# MCU.net
KiCad netlist of a schematic drawn in Altium Designer
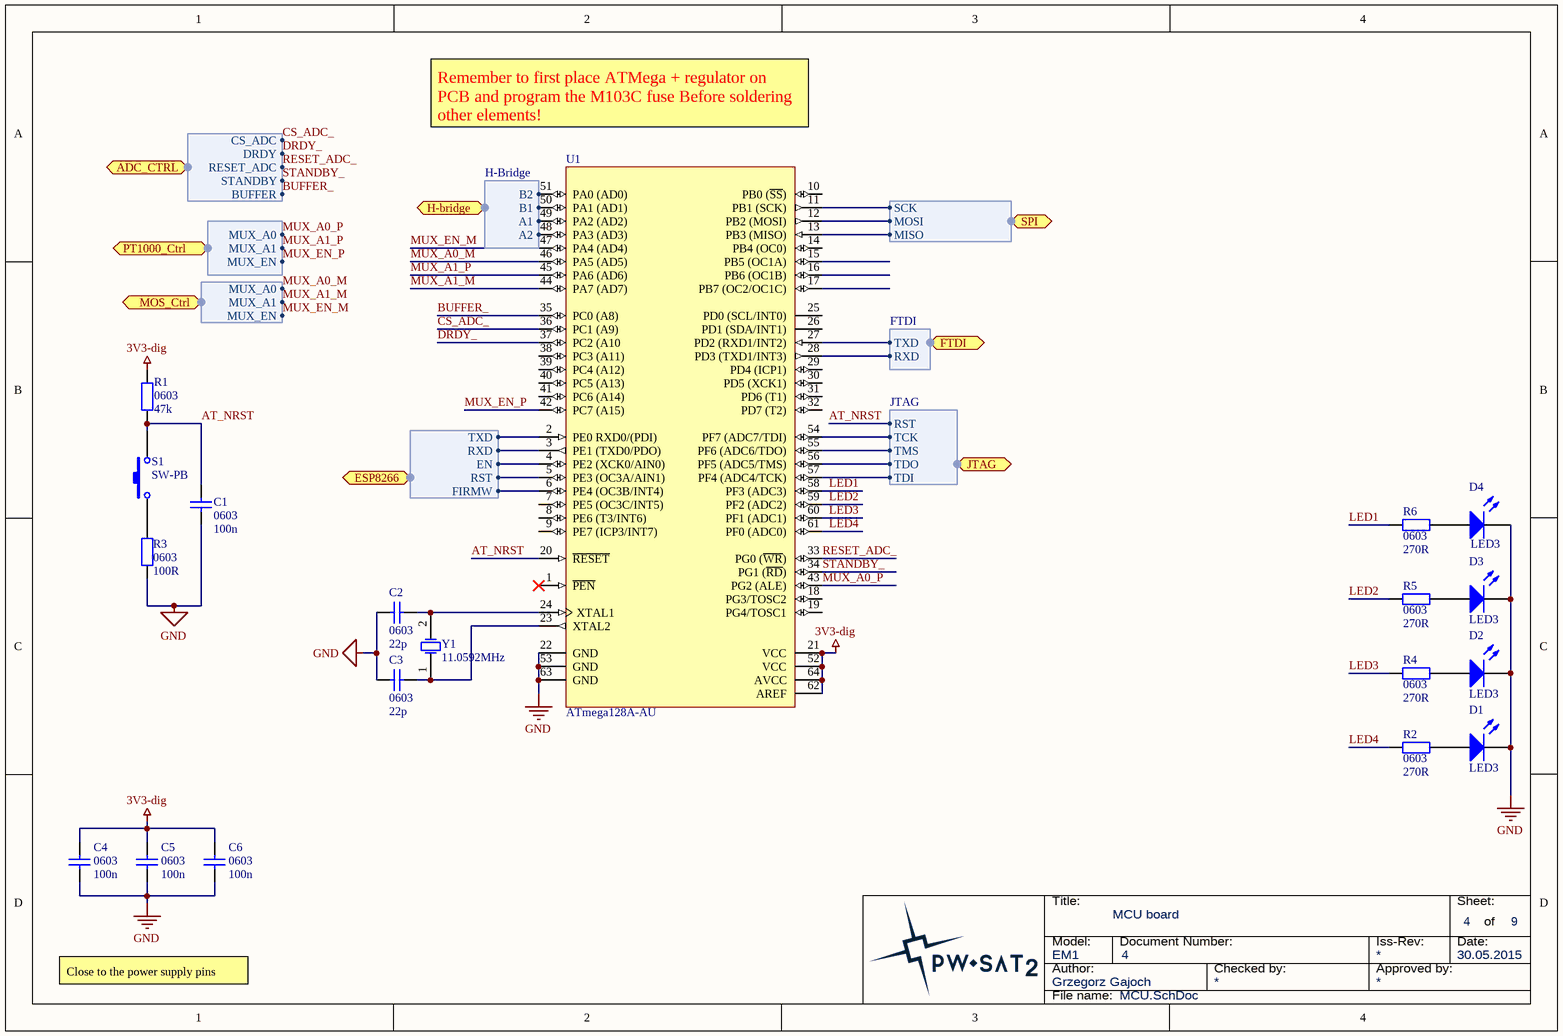
[diagram p0: MCU.SchDoc]

(export (version "E")
  (design (tool "Eeschema 10.0.6"))
  (components
    (comp (ref "C1")
      (value "0603")
      (footprint "SMD_Capacitor_0603")
      (description "Capacitor")
      (fields (field (name "ALTIUM_VALUE") "100n") (field (name "PUBLISHER") "Altium Limited"))
      (libsource (lib "Miscellaneous Devices") (part "Cap"))
    )
    (comp (ref "C2")
      (value "0603")
      (footprint "SMD_Capacitor_0603")
      (description "Capacitor")
      (fields (field (name "ALTIUM_VALUE") "22p") (field (name "PUBLISHER") "Altium Limited"))
      (libsource (lib "Miscellaneous Devices") (part "Cap"))
    )
    (comp (ref "C3")
      (value "0603")
      (footprint "SMD_Capacitor_0603")
      (description "Capacitor")
      (fields (field (name "ALTIUM_VALUE") "22p") (field (name "PUBLISHER") "Altium Limited"))
      (libsource (lib "Miscellaneous Devices") (part "Cap"))
    )
    (comp (ref "C4")
      (value "0603")
      (footprint "SMD_Capacitor_0603")
      (description "Capacitor")
      (fields (field (name "ALTIUM_VALUE") "100n") (field (name "PUBLISHER") "Altium Limited"))
      (libsource (lib "Miscellaneous Devices") (part "Cap"))
    )
    (comp (ref "C5")
      (value "0603")
      (footprint "SMD_Capacitor_0603")
      (description "Capacitor")
      (fields (field (name "ALTIUM_VALUE") "100n") (field (name "PUBLISHER") "Altium Limited"))
      (libsource (lib "Miscellaneous Devices") (part "Cap"))
    )
    (comp (ref "C6")
      (value "0603")
      (footprint "SMD_Capacitor_0603")
      (description "Capacitor")
      (fields (field (name "ALTIUM_VALUE") "100n") (field (name "PUBLISHER") "Altium Limited"))
      (libsource (lib "Miscellaneous Devices") (part "Cap"))
    )
    (comp (ref "D1")
      (value "LED3")
      (footprint "LED 0805 RED")
      (description "Typical BLUE SiC LED")
      (fields (field (name "PUBLISHER") "Altium Limited"))
      (libsource (lib "Miscellaneous Devices") (part "LED3"))
    )
    (comp (ref "D2")
      (value "LED3")
      (footprint "LED 0805 GREEN")
      (description "Typical BLUE SiC LED")
      (fields (field (name "PUBLISHER") "Altium Limited"))
      (libsource (lib "Miscellaneous Devices") (part "LED3"))
    )
    (comp (ref "D3")
      (value "LED3")
      (footprint "LED 0805 Yellow")
      (description "Typical BLUE SiC LED")
      (fields (field (name "PUBLISHER") "Altium Limited"))
      (libsource (lib "Miscellaneous Devices") (part "LED3"))
    )
    (comp (ref "D4")
      (value "LED3")
      (footprint "LED 0805 Blue")
      (description "Typical BLUE SiC LED")
      (fields (field (name "PUBLISHER") "Altium Limited"))
      (libsource (lib "Miscellaneous Devices") (part "LED3"))
    )
    (comp (ref "R1")
      (value "0603")
      (footprint "SMD_Resistor_0603")
      (description "Resistor")
      (fields (field (name "ALTIUM_VALUE") "47k") (field (name "PUBLISHER") "Altium Limited"))
      (libsource (lib "Miscellaneous Devices") (part "Res2"))
    )
    (comp (ref "R2")
      (value "0603")
      (footprint "SMD_Resistor_0603")
      (description "Resistor")
      (fields (field (name "ALTIUM_VALUE") "270R") (field (name "PUBLISHER") "Altium Limited"))
      (libsource (lib "") (part "Res2_1"))
    )
    (comp (ref "R3")
      (value "0603")
      (footprint "SMD_Resistor_0603")
      (description "Resistor")
      (fields (field (name "ALTIUM_VALUE") "100R") (field (name "PUBLISHER") "Altium Limited"))
      (libsource (lib "") (part "Res2_2"))
    )
    (comp (ref "R4")
      (value "0603")
      (footprint "SMD_Resistor_0603")
      (description "Resistor")
      (fields (field (name "ALTIUM_VALUE") "270R") (field (name "PUBLISHER") "Altium Limited"))
      (libsource (lib "") (part "Res2_1"))
    )
    (comp (ref "R5")
      (value "0603")
      (footprint "SMD_Resistor_0603")
      (description "Resistor")
      (fields (field (name "ALTIUM_VALUE") "270R") (field (name "PUBLISHER") "Altium Limited"))
      (libsource (lib "") (part "Res2_1"))
    )
    (comp (ref "R6")
      (value "0603")
      (footprint "SMD_Resistor_0603")
      (description "Resistor")
      (fields (field (name "ALTIUM_VALUE") "270R") (field (name "PUBLISHER") "Altium Limited"))
      (libsource (lib "") (part "Res2_1"))
    )
    (comp (ref "S1")
      (value "SW-PB")
      (footprint "Tact Switch 3x6")
      (description "Switch")
      (fields (field (name "PUBLISHER") "Altium Limited"))
      (libsource (lib "Miscellaneous Devices") (part "SW-PB"))
    )
    (comp (ref "U1")
      (value "ATmega128A-AU")
      (footprint "64A_M")
      (libsource (lib "Atmel Microcontroller megaAVR") (part "ATmega128A-AU"))
    )
    (comp (ref "Y1")
      (value "11.0592MHz")
      (footprint "Quartz")
      (description "LF XTAL003519")
      (fields (field (name "PUBLISHER") "Altium Limited"))
      (libsource (lib "Miscellaneous Devices") (part "XTAL"))
    )
  )
  (nets
    (net (code "8") (name "/A1") (class "Default")
      (node (ref "U1") (pin "49") (pinfunction "PA2_(AD2)_49") (pintype "bidirectional"))
    )
    (net (code "9") (name "/A2") (class "Default")
      (node (ref "U1") (pin "48") (pinfunction "PA3_(AD3)_48") (pintype "bidirectional"))
    )
    (net (code "10") (name "/AT_NRST") (class "Default")
      (node (ref "C1") (pin "2") (pinfunction "2_2") (pintype "passive"))
      (node (ref "R1") (pin "1") (pinfunction "1_1") (pintype "passive"))
      (node (ref "S1") (pin "2") (pinfunction "2_2") (pintype "passive"))
      (node (ref "U1") (pin "20") (pinfunction "~{RESET}_20") (pintype "input"))
    )
    (net (code "11") (name "/B1") (class "Default")
      (node (ref "U1") (pin "50") (pinfunction "PA1_(AD1)_50") (pintype "bidirectional"))
    )
    (net (code "12") (name "/B2") (class "Default")
      (node (ref "U1") (pin "51") (pinfunction "PA0_(AD0)_51") (pintype "bidirectional"))
    )
    (net (code "13") (name "/BUFFER_") (class "Default")
      (node (ref "U1") (pin "35") (pinfunction "PC0_(A8)_35") (pintype "bidirectional"))
    )
    (net (code "14") (name "/CS_ADC_") (class "Default")
      (node (ref "U1") (pin "36") (pinfunction "PC1_(A9)_36") (pintype "bidirectional"))
    )
    (net (code "15") (name "/DRDY_") (class "Default")
      (node (ref "U1") (pin "37") (pinfunction "PC2_(A10_37") (pintype "bidirectional"))
    )
    (net (code "16") (name "/EN") (class "Default")
      (node (ref "U1") (pin "4") (pinfunction "PE2_(XCK0/AIN0)_4") (pintype "bidirectional"))
    )
    (net (code "17") (name "/FIRMW") (class "Default")
      (node (ref "U1") (pin "6") (pinfunction "PE4_(OC3B/INT4)_6") (pintype "bidirectional"))
    )
    (net (code "18") (name "/LED1") (class "Default")
      (node (ref "R6") (pin "2") (pinfunction "2_2") (pintype "passive"))
      (node (ref "U1") (pin "58") (pinfunction "PF3_(ADC3)_58") (pintype "bidirectional"))
    )
    (net (code "19") (name "/LED2") (class "Default")
      (node (ref "R5") (pin "2") (pinfunction "2_2") (pintype "passive"))
      (node (ref "U1") (pin "59") (pinfunction "PF2_(ADC2)_59") (pintype "bidirectional"))
    )
    (net (code "20") (name "/LED3") (class "Default")
      (node (ref "R4") (pin "2") (pinfunction "2_2") (pintype "passive"))
      (node (ref "U1") (pin "60") (pinfunction "PF1_(ADC1)_60") (pintype "bidirectional"))
    )
    (net (code "21") (name "/LED4") (class "Default")
      (node (ref "R2") (pin "2") (pinfunction "2_2") (pintype "passive"))
      (node (ref "U1") (pin "61") (pinfunction "PF0_(ADC0)_61") (pintype "bidirectional"))
    )
    (net (code "22") (name "/MISO") (class "Default")
      (node (ref "U1") (pin "13") (pinfunction "PB3_(MISO)_13") (pintype "input"))
    )
    (net (code "23") (name "/MOSI") (class "Default")
      (node (ref "U1") (pin "12") (pinfunction "PB2_(MOSI)_12") (pintype "output"))
    )
    (net (code "24") (name "/MUX_A0_M") (class "Default")
      (node (ref "U1") (pin "46") (pinfunction "PA5_(AD5)_46") (pintype "bidirectional"))
    )
    (net (code "25") (name "/MUX_A0_P") (class "Default")
      (node (ref "U1") (pin "43") (pinfunction "PG2_(ALE)_43") (pintype "bidirectional"))
    )
    (net (code "26") (name "/MUX_A1_M") (class "Default")
      (node (ref "U1") (pin "44") (pinfunction "PA7_(AD7)_44") (pintype "bidirectional"))
    )
    (net (code "27") (name "/MUX_A1_P") (class "Default")
      (node (ref "U1") (pin "45") (pinfunction "PA6_(AD6)_45") (pintype "bidirectional"))
    )
    (net (code "28") (name "/MUX_EN_M") (class "Default")
      (node (ref "U1") (pin "47") (pinfunction "PA4_(AD4)_47") (pintype "bidirectional"))
    )
    (net (code "29") (name "/MUX_EN_P") (class "Default")
      (node (ref "U1") (pin "42") (pinfunction "PC7_(A15)_42") (pintype "bidirectional"))
    )
    (net (code "30") (name "/RESET_ADC_") (class "Default")
      (node (ref "U1") (pin "33") (pinfunction "PG0_(~{WR})_33") (pintype "bidirectional"))
    )
    (net (code "31") (name "/SCK") (class "Default")
      (node (ref "U1") (pin "11") (pinfunction "PB1_(SCK)_11") (pintype "output"))
    )
    (net (code "32") (name "/STANDBY_") (class "Default")
      (node (ref "U1") (pin "34") (pinfunction "PG1_(~{RD})_34") (pintype "bidirectional"))
    )
    (net (code "33") (name "/TCK") (class "Default")
      (node (ref "U1") (pin "54") (pinfunction "PF7_(ADC7/TDI)_54") (pintype "bidirectional"))
    )
    (net (code "34") (name "/TDI") (class "Default")
      (node (ref "U1") (pin "57") (pinfunction "PF4_(ADC4/TCK)_57") (pintype "bidirectional"))
    )
    (net (code "35") (name "/TDO") (class "Default")
      (node (ref "U1") (pin "56") (pinfunction "PF5_(ADC5/TMS)_56") (pintype "bidirectional"))
    )
    (net (code "36") (name "/TMS") (class "Default")
      (node (ref "U1") (pin "55") (pinfunction "PF6_(ADC6/TDO)_55") (pintype "bidirectional"))
    )
    (net (code "44") (name "3V3-dig") (class "Default")
      (node (ref "C4") (pin "2") (pinfunction "2_2") (pintype "passive"))
      (node (ref "C5") (pin "2") (pinfunction "2_2") (pintype "passive"))
      (node (ref "C6") (pin "2") (pinfunction "2_2") (pintype "passive"))
      (node (ref "R1") (pin "2") (pinfunction "2_2") (pintype "passive"))
      (node (ref "U1") (pin "21") (pinfunction "VCC_21") (pintype "power_in"))
      (node (ref "U1") (pin "52") (pinfunction "VCC_52") (pintype "power_in"))
      (node (ref "U1") (pin "62") (pinfunction "AREF_62") (pintype "power_in"))
      (node (ref "U1") (pin "64") (pinfunction "AVCC_64") (pintype "power_in"))
    )
    (net (code "45") (name "GND") (class "Default")
      (node (ref "C1") (pin "1") (pinfunction "1_1") (pintype "passive"))
      (node (ref "C2") (pin "1") (pinfunction "1_1") (pintype "passive"))
      (node (ref "C3") (pin "1") (pinfunction "1_1") (pintype "passive"))
      (node (ref "C4") (pin "1") (pinfunction "1_1") (pintype "passive"))
      (node (ref "C5") (pin "1") (pinfunction "1_1") (pintype "passive"))
      (node (ref "C6") (pin "1") (pinfunction "1_1") (pintype "passive"))
      (node (ref "D1") (pin "2") (pinfunction "K_2") (pintype "passive"))
      (node (ref "D2") (pin "2") (pinfunction "K_2") (pintype "passive"))
      (node (ref "D3") (pin "2") (pinfunction "K_2") (pintype "passive"))
      (node (ref "D4") (pin "2") (pinfunction "K_2") (pintype "passive"))
      (node (ref "R3") (pin "2") (pinfunction "2_2") (pintype "passive"))
      (node (ref "U1") (pin "22") (pinfunction "GND_22") (pintype "power_in"))
      (node (ref "U1") (pin "53") (pinfunction "GND_53") (pintype "power_in"))
      (node (ref "U1") (pin "63") (pinfunction "GND_63") (pintype "power_in"))
    )
    (net (code "46") (name "Net-(D1-A)") (class "Default")
      (node (ref "D1") (pin "1") (pinfunction "A_1") (pintype "passive"))
      (node (ref "R2") (pin "1") (pinfunction "1_1") (pintype "passive"))
    )
    (net (code "47") (name "Net-(D2-A)") (class "Default")
      (node (ref "D2") (pin "1") (pinfunction "A_1") (pintype "passive"))
      (node (ref "R4") (pin "1") (pinfunction "1_1") (pintype "passive"))
    )
    (net (code "48") (name "Net-(D3-A)") (class "Default")
      (node (ref "D3") (pin "1") (pinfunction "A_1") (pintype "passive"))
      (node (ref "R5") (pin "1") (pinfunction "1_1") (pintype "passive"))
    )
    (net (code "49") (name "Net-(D4-A)") (class "Default")
      (node (ref "D4") (pin "1") (pinfunction "A_1") (pintype "passive"))
      (node (ref "R6") (pin "1") (pinfunction "1_1") (pintype "passive"))
    )
    (net (code "50") (name "Net-(R3-Pad1)") (class "Default")
      (node (ref "R3") (pin "1") (pinfunction "1_1") (pintype "passive"))
      (node (ref "S1") (pin "1") (pinfunction "1_1") (pintype "passive"))
    )
    (net (code "51") (name "Net-(U1-XTAL1)") (class "Default")
      (node (ref "C2") (pin "2") (pinfunction "2_2") (pintype "passive"))
      (node (ref "U1") (pin "24") (pinfunction "XTAL1_24") (pintype "input"))
      (node (ref "Y1") (pin "2") (pinfunction "OSC2_2") (pintype "passive"))
    )
    (net (code "52") (name "Net-(U1-XTAL2)") (class "Default")
      (node (ref "C3") (pin "2") (pinfunction "2_2") (pintype "passive"))
      (node (ref "U1") (pin "23") (pinfunction "XTAL2_23") (pintype "output"))
      (node (ref "Y1") (pin "1") (pinfunction "OSC1_1") (pintype "passive"))
    )
    (net (code "53") (name "unconnected-(U1-PB0_(~{SS})-Pad10)") (class "Default")
      (node (ref "U1") (pin "10") (pinfunction "PB0_(~{SS})_10") (pintype "bidirectional"))
    )
    (net (code "54") (name "unconnected-(U1-PB4_(OC0)-Pad14)") (class "Default")
      (node (ref "U1") (pin "14") (pinfunction "PB4_(OC0)_14") (pintype "bidirectional"))
    )
    (net (code "55") (name "unconnected-(U1-PB5_(OC1A)-Pad15)") (class "Default")
      (node (ref "U1") (pin "15") (pinfunction "PB5_(OC1A)_15") (pintype "bidirectional"))
    )
    (net (code "56") (name "unconnected-(U1-PB6_(OC1B)-Pad16)") (class "Default")
      (node (ref "U1") (pin "16") (pinfunction "PB6_(OC1B)_16") (pintype "bidirectional"))
    )
    (net (code "57") (name "unconnected-(U1-PB7_(OC2{slash}OC1C)-Pad17)") (class "Default")
      (node (ref "U1") (pin "17") (pinfunction "PB7_(OC2/OC1C)_17") (pintype "bidirectional"))
    )
    (net (code "58") (name "unconnected-(U1-PC3_(A11)-Pad38)") (class "Default")
      (node (ref "U1") (pin "38") (pinfunction "PC3_(A11)_38") (pintype "bidirectional"))
    )
    (net (code "59") (name "unconnected-(U1-PC4_(A12)-Pad39)") (class "Default")
      (node (ref "U1") (pin "39") (pinfunction "PC4_(A12)_39") (pintype "bidirectional"))
    )
    (net (code "60") (name "unconnected-(U1-PC5_(A13)-Pad40)") (class "Default")
      (node (ref "U1") (pin "40") (pinfunction "PC5_(A13)_40") (pintype "bidirectional"))
    )
    (net (code "61") (name "unconnected-(U1-PC6_(A14)-Pad41)") (class "Default")
      (node (ref "U1") (pin "41") (pinfunction "PC6_(A14)_41") (pintype "bidirectional"))
    )
    (net (code "62") (name "unconnected-(U1-PD0_(SCL{slash}INT0)-Pad25)") (class "Default")
      (node (ref "U1") (pin "25") (pinfunction "PD0_(SCL/INT0)_25") (pintype "open_collector"))
    )
    (net (code "63") (name "unconnected-(U1-PD1_(SDA{slash}INT1)-Pad26)") (class "Default")
      (node (ref "U1") (pin "26") (pinfunction "PD1_(SDA/INT1)_26") (pintype "open_collector"))
    )
    (net (code "64") (name "unconnected-(U1-PD2_(RXD1{slash}INT2)-Pad27)") (class "Default")
      (node (ref "U1") (pin "27") (pinfunction "PD2_(RXD1/INT2)_27") (pintype "input"))
    )
    (net (code "65") (name "unconnected-(U1-PD3_(TXD1{slash}INT3)-Pad28)") (class "Default")
      (node (ref "U1") (pin "28") (pinfunction "PD3_(TXD1/INT3)_28") (pintype "output"))
    )
    (net (code "66") (name "unconnected-(U1-PD4_(ICP1)-Pad29)") (class "Default")
      (node (ref "U1") (pin "29") (pinfunction "PD4_(ICP1)_29") (pintype "bidirectional"))
    )
    (net (code "67") (name "unconnected-(U1-PD5_(XCK1)-Pad30)") (class "Default")
      (node (ref "U1") (pin "30") (pinfunction "PD5_(XCK1)_30") (pintype "bidirectional"))
    )
    (net (code "68") (name "unconnected-(U1-PD6_(T1)-Pad31)") (class "Default")
      (node (ref "U1") (pin "31") (pinfunction "PD6_(T1)_31") (pintype "bidirectional"))
    )
    (net (code "69") (name "unconnected-(U1-PD7_(T2)-Pad32)") (class "Default")
      (node (ref "U1") (pin "32") (pinfunction "PD7_(T2)_32") (pintype "bidirectional"))
    )
    (net (code "70") (name "unconnected-(U1-PE0_RXD0{slash}(PDI)-Pad2)") (class "Default")
      (node (ref "U1") (pin "2") (pinfunction "PE0_RXD0/(PDI)_2") (pintype "input"))
    )
    (net (code "71") (name "unconnected-(U1-PE1_(TXD0{slash}PDO)-Pad3)") (class "Default")
      (node (ref "U1") (pin "3") (pinfunction "PE1_(TXD0/PDO)_3") (pintype "output"))
    )
    (net (code "72") (name "unconnected-(U1-PE3_(OC3A{slash}AIN1)-Pad5)") (class "Default")
      (node (ref "U1") (pin "5") (pinfunction "PE3_(OC3A/AIN1)_5") (pintype "bidirectional"))
    )
    (net (code "73") (name "unconnected-(U1-PE5_(OC3C{slash}INT5)-Pad7)") (class "Default")
      (node (ref "U1") (pin "7") (pinfunction "PE5_(OC3C/INT5)_7") (pintype "bidirectional"))
    )
    (net (code "74") (name "unconnected-(U1-PE6_(T3{slash}INT6)-Pad8)") (class "Default")
      (node (ref "U1") (pin "8") (pinfunction "PE6_(T3/INT6)_8") (pintype "bidirectional"))
    )
    (net (code "75") (name "unconnected-(U1-PE7_(ICP3{slash}INT7)-Pad9)") (class "Default")
      (node (ref "U1") (pin "9") (pinfunction "PE7_(ICP3/INT7)_9") (pintype "bidirectional"))
    )
    (net (code "76") (name "unconnected-(U1-PG3{slash}TOSC2-Pad18)") (class "Default")
      (node (ref "U1") (pin "18") (pinfunction "PG3/TOSC2_18") (pintype "bidirectional"))
    )
    (net (code "77") (name "unconnected-(U1-PG4{slash}TOSC1-Pad19)") (class "Default")
      (node (ref "U1") (pin "19") (pinfunction "PG4/TOSC1_19") (pintype "bidirectional"))
    )
    (net (code "78") (name "unconnected-(U1-~{PEN}-Pad1)") (class "Default")
      (node (ref "U1") (pin "1") (pinfunction "~{PEN}_1") (pintype "input+no_connect"))
    )
  )
)
